# iTag3Sensors2.net
KiCad netlist of a schematic drawn in Altium Designer
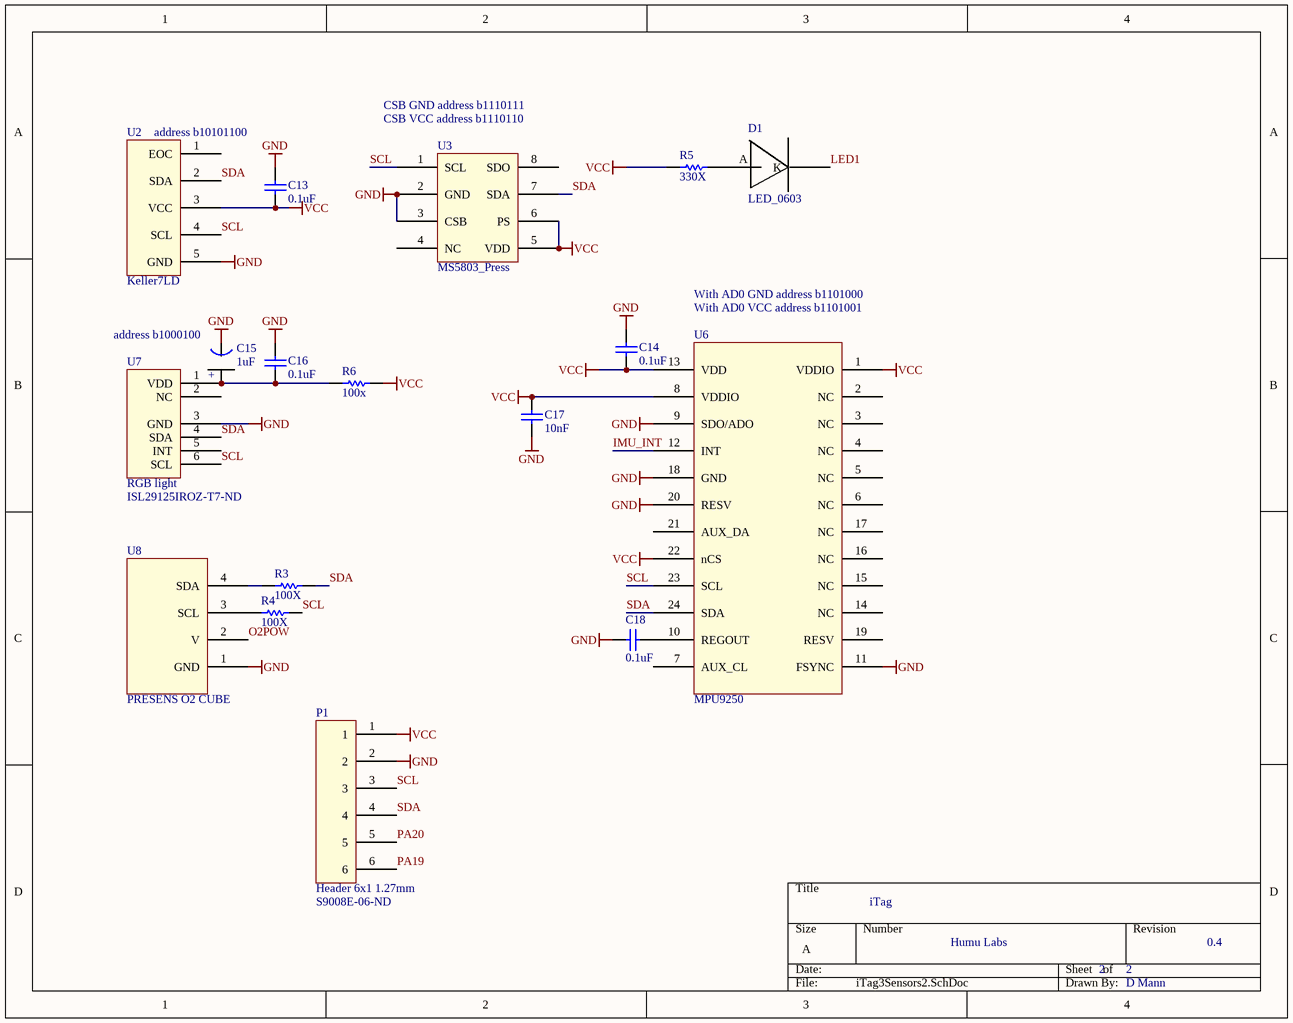
[diagram p0: iTag3Sensors2.SchDoc]

(export (version "E")
  (design (tool "Eeschema 10.0.6"))
  (components
    (comp (ref "C13")
      (value "0.1uF")
      (footprint "0402")
      (description "Ceramic Chip Capacitor - Standard")
      (fields (field (name "PUBLISHER") "Altium Limited"))
      (libsource (lib "KEMET Chip Capacitor") (part "C0402"))
    )
    (comp (ref "C14")
      (value "0.1uF")
      (footprint "0402")
      (description "Ceramic Chip Capacitor - Standard")
      (fields (field (name "PUBLISHER") "Altium Limited"))
      (libsource (lib "KEMET Chip Capacitor") (part "C0402"))
    )
    (comp (ref "C15") (value "1uF") (footprint "Tant0805") (libsource (lib "Loggerhead") (part "Tant0805")))
    (comp (ref "C16")
      (value "0.1uF")
      (footprint "0402")
      (description "Ceramic Chip Capacitor - Standard")
      (fields (field (name "PUBLISHER") "Altium Limited"))
      (libsource (lib "KEMET Chip Capacitor") (part "C0402"))
    )
    (comp (ref "C17")
      (value "10nF")
      (footprint "0402")
      (description "Ceramic Chip Capacitor - Standard")
      (fields (field (name "PUBLISHER") "Altium Limited"))
      (libsource (lib "KEMET Chip Capacitor") (part "C0402"))
    )
    (comp (ref "C18")
      (value "0.1uF")
      (footprint "0402")
      (description "Ceramic Chip Capacitor - Standard")
      (fields (field (name "PUBLISHER") "Altium Limited"))
      (libsource (lib "KEMET Chip Capacitor") (part "C0402"))
    )
    (comp (ref "D1")
      (value "LED_0603")
      (footprint "Diode0603")
      (libsource (lib "Loggerhead") (part "LED_0603"))
    )
    (comp (ref "P1")
      (value "Header 6x1 1.27mm")
      (footprint "Header6x1 1.27mm")
      (fields (field (name "SUPPLIER PART NUMBER 1") "S9008E-06-ND"))
      (libsource (lib "Loggerhead") (part "Header 6x1 1.27mm"))
    )
    (comp (ref "R3")
      (value "100X")
      (footprint "3-0603")
      (fields (field (name "PUBLISHER") "Altium Limited"))
      (libsource (lib "Panasonic Resistor") (part "ERJ3RK"))
    )
    (comp (ref "R4")
      (value "100X")
      (footprint "3-0603")
      (fields (field (name "PUBLISHER") "Altium Limited"))
      (libsource (lib "Panasonic Resistor") (part "ERJ3RK"))
    )
    (comp (ref "R5")
      (value "330X")
      (footprint "3-0603")
      (fields (field (name "PUBLISHER") "Altium Limited"))
      (libsource (lib "Panasonic Resistor") (part "ERJ3RK"))
    )
    (comp (ref "R6")
      (value "100x")
      (footprint "3-0603")
      (fields (field (name "PUBLISHER") "Altium Limited"))
      (libsource (lib "Panasonic Resistor") (part "ERJ3RK"))
    )
    (comp (ref "U2")
      (value "Keller7LD")
      (footprint "Keller7LD")
      (description "Keller Pressure/Temp")
      (libsource (lib "Loggerhead") (part "Keller 7LD"))
    )
    (comp (ref "U3")
      (value "MS5803_Press")
      (footprint "MS5803_Press")
      (libsource (lib "Loggerhead") (part "MS5803_Press"))
    )
    (comp (ref "U6")
      (value "MPU9250")
      (footprint "MPU6500")
      (description "Invensense")
      (libsource (lib "Loggerhead") (part "MPU-9250"))
    )
    (comp (ref "U7")
      (value "RGB light")
      (footprint "ODFN")
      (description "RGB light sensor")
      (fields (field (name "SUPPLIER PART NUMBER 1") "ISL29125IROZ-T7-ND"))
      (libsource (lib "Loggerhead") (part "ISL29125"))
    )
    (comp (ref "U8")
      (value "PRESENS O2 CUBE")
      (footprint "PRESENS_O2")
      (libsource (lib "Loggerhead") (part "PRESENS_O2"))
    )
  )
  (nets
    (net (code "1") (name "/IMU_INT") (class "Default")
      (node (ref "U6") (pin "12") (pinfunction "INT_12") (pintype "passive"))
    )
    (net (code "2") (name "/LED1") (class "Default")
      (node (ref "D1") (pin "K") (pinfunction "K_K") (pintype "passive"))
    )
    (net (code "3") (name "/O2POW") (class "Default")
      (node (ref "U8") (pin "2") (pinfunction "V_2") (pintype "passive"))
    )
    (net (code "4") (name "/PA19") (class "Default")
      (node (ref "P1") (pin "6") (pinfunction "6_6") (pintype "passive"))
    )
    (net (code "5") (name "/PA20") (class "Default")
      (node (ref "P1") (pin "5") (pinfunction "5_5") (pintype "passive"))
    )
    (net (code "6") (name "/SCL") (class "Default")
      (node (ref "P1") (pin "3") (pinfunction "3_3") (pintype "passive"))
      (node (ref "R4") (pin "2") (pinfunction "2_2") (pintype "passive"))
      (node (ref "U2") (pin "4") (pinfunction "SCL_4") (pintype "passive"))
      (node (ref "U3") (pin "1") (pinfunction "SCL_1") (pintype "passive"))
      (node (ref "U6") (pin "23") (pinfunction "SCL_23") (pintype "passive"))
      (node (ref "U7") (pin "6") (pinfunction "SCL_6") (pintype "passive"))
    )
    (net (code "7") (name "/SDA") (class "Default")
      (node (ref "P1") (pin "4") (pinfunction "4_4") (pintype "passive"))
      (node (ref "R3") (pin "2") (pinfunction "2_2") (pintype "passive"))
      (node (ref "U2") (pin "2") (pinfunction "SDA_2") (pintype "passive"))
      (node (ref "U3") (pin "7") (pinfunction "SDA_7") (pintype "passive"))
      (node (ref "U6") (pin "24") (pinfunction "SDA_24") (pintype "passive"))
      (node (ref "U7") (pin "4") (pinfunction "SDA_4") (pintype "passive"))
    )
    (net (code "8") (name "GND") (class "Default")
      (node (ref "C13") (pin "2") (pinfunction "2_2") (pintype "passive"))
      (node (ref "C14") (pin "2") (pinfunction "2_2") (pintype "passive"))
      (node (ref "C15") (pin "1") (pinfunction "GND_1") (pintype "passive"))
      (node (ref "C16") (pin "2") (pinfunction "2_2") (pintype "passive"))
      (node (ref "C17") (pin "2") (pinfunction "2_2") (pintype "passive"))
      (node (ref "C18") (pin "1") (pinfunction "1_1") (pintype "passive"))
      (node (ref "P1") (pin "2") (pinfunction "2_2") (pintype "passive"))
      (node (ref "U2") (pin "5") (pinfunction "GND_5") (pintype "passive"))
      (node (ref "U3") (pin "2") (pinfunction "GND_2") (pintype "passive"))
      (node (ref "U3") (pin "3") (pinfunction "CSB_3") (pintype "passive"))
      (node (ref "U6") (pin "11") (pinfunction "FSYNC_11") (pintype "passive"))
      (node (ref "U6") (pin "18") (pinfunction "GND_18") (pintype "passive"))
      (node (ref "U6") (pin "20") (pinfunction "RESV_20") (pintype "passive"))
      (node (ref "U6") (pin "9") (pinfunction "SDO/ADO_9") (pintype "passive"))
      (node (ref "U7") (pin "3") (pinfunction "GND_3") (pintype "passive"))
      (node (ref "U8") (pin "1") (pinfunction "GND_1") (pintype "passive"))
    )
    (net (code "9") (name "Net-(C15-+)") (class "Default")
      (node (ref "C15") (pin "2") (pinfunction "+_2") (pintype "passive"))
      (node (ref "C16") (pin "1") (pinfunction "1_1") (pintype "passive"))
      (node (ref "R6") (pin "2") (pinfunction "2_2") (pintype "passive"))
      (node (ref "U7") (pin "1") (pinfunction "VDD_1") (pintype "passive"))
    )
    (net (code "10") (name "Net-(D1-PadA)") (class "Default")
      (node (ref "D1") (pin "A") (pinfunction "A_A") (pintype "passive"))
      (node (ref "R5") (pin "2") (pinfunction "2_2") (pintype "passive"))
    )
    (net (code "11") (name "Net-(U6-REGOUT)") (class "Default")
      (node (ref "C18") (pin "2") (pinfunction "2_2") (pintype "passive"))
      (node (ref "U6") (pin "10") (pinfunction "REGOUT_10") (pintype "passive"))
    )
    (net (code "12") (name "Net-(U8-SCL)") (class "Default")
      (node (ref "R4") (pin "1") (pinfunction "1_1") (pintype "passive"))
      (node (ref "U8") (pin "3") (pinfunction "SCL_3") (pintype "passive"))
    )
    (net (code "13") (name "Net-(U8-SDA)") (class "Default")
      (node (ref "R3") (pin "1") (pinfunction "1_1") (pintype "passive"))
      (node (ref "U8") (pin "4") (pinfunction "SDA_4") (pintype "passive"))
    )
    (net (code "14") (name "VCC") (class "Default")
      (node (ref "C13") (pin "1") (pinfunction "1_1") (pintype "passive"))
      (node (ref "C14") (pin "1") (pinfunction "1_1") (pintype "passive"))
      (node (ref "C17") (pin "1") (pinfunction "1_1") (pintype "passive"))
      (node (ref "P1") (pin "1") (pinfunction "1_1") (pintype "passive"))
      (node (ref "R5") (pin "1") (pinfunction "1_1") (pintype "passive"))
      (node (ref "R6") (pin "1") (pinfunction "1_1") (pintype "passive"))
      (node (ref "U2") (pin "3") (pinfunction "VCC_3") (pintype "passive"))
      (node (ref "U3") (pin "5") (pinfunction "VDD_5") (pintype "power_in"))
      (node (ref "U3") (pin "6") (pinfunction "PS_6") (pintype "passive"))
      (node (ref "U6") (pin "1") (pinfunction "VDDIO_1") (pintype "passive"))
      (node (ref "U6") (pin "13") (pinfunction "VDD_13") (pintype "passive"))
      (node (ref "U6") (pin "22") (pinfunction "nCS_22") (pintype "passive"))
      (node (ref "U6") (pin "8") (pinfunction "VDDIO_8") (pintype "passive"))
    )
    (net (code "15") (name "unconnected-(U2-EOC-Pad1)") (class "Default")
      (node (ref "U2") (pin "1") (pinfunction "EOC_1") (pintype "passive"))
    )
    (net (code "16") (name "unconnected-(U3-NC-Pad4)") (class "Default")
      (node (ref "U3") (pin "4") (pinfunction "NC_4") (pintype "passive"))
    )
    (net (code "17") (name "unconnected-(U3-SDO-Pad8)") (class "Default")
      (node (ref "U3") (pin "8") (pinfunction "SDO_8") (pintype "passive"))
    )
    (net (code "18") (name "unconnected-(U6-AUX_CL-Pad7)") (class "Default")
      (node (ref "U6") (pin "7") (pinfunction "AUX_CL_7") (pintype "passive"))
    )
    (net (code "19") (name "unconnected-(U6-AUX_DA-Pad21)") (class "Default")
      (node (ref "U6") (pin "21") (pinfunction "AUX_DA_21") (pintype "passive"))
    )
    (net (code "20") (name "unconnected-(U6-NC-Pad2)") (class "Default")
      (node (ref "U6") (pin "2") (pinfunction "NC_2") (pintype "passive"))
    )
    (net (code "21") (name "unconnected-(U6-NC-Pad3)") (class "Default")
      (node (ref "U6") (pin "3") (pinfunction "NC_3") (pintype "passive"))
    )
    (net (code "22") (name "unconnected-(U6-NC-Pad4)") (class "Default")
      (node (ref "U6") (pin "4") (pinfunction "NC_4") (pintype "passive"))
    )
    (net (code "23") (name "unconnected-(U6-NC-Pad5)") (class "Default")
      (node (ref "U6") (pin "5") (pinfunction "NC_5") (pintype "passive"))
    )
    (net (code "24") (name "unconnected-(U6-NC-Pad6)") (class "Default")
      (node (ref "U6") (pin "6") (pinfunction "NC_6") (pintype "passive"))
    )
    (net (code "25") (name "unconnected-(U6-NC-Pad14)") (class "Default")
      (node (ref "U6") (pin "14") (pinfunction "NC_14") (pintype "passive"))
    )
    (net (code "26") (name "unconnected-(U6-NC-Pad15)") (class "Default")
      (node (ref "U6") (pin "15") (pinfunction "NC_15") (pintype "passive"))
    )
    (net (code "27") (name "unconnected-(U6-NC-Pad16)") (class "Default")
      (node (ref "U6") (pin "16") (pinfunction "NC_16") (pintype "passive"))
    )
    (net (code "28") (name "unconnected-(U6-NC-Pad17)") (class "Default")
      (node (ref "U6") (pin "17") (pinfunction "NC_17") (pintype "passive"))
    )
    (net (code "29") (name "unconnected-(U6-RESV-Pad19)") (class "Default")
      (node (ref "U6") (pin "19") (pinfunction "RESV_19") (pintype "passive"))
    )
    (net (code "30") (name "unconnected-(U7-INT-Pad5)") (class "Default")
      (node (ref "U7") (pin "5") (pinfunction "INT_5") (pintype "passive"))
    )
    (net (code "31") (name "unconnected-(U7-NC-Pad2)") (class "Default")
      (node (ref "U7") (pin "2") (pinfunction "NC_2") (pintype "passive"))
    )
  )
)
